# External_Power_Amplifier.net
KiCad netlist of a schematic drawn in Altium Designer
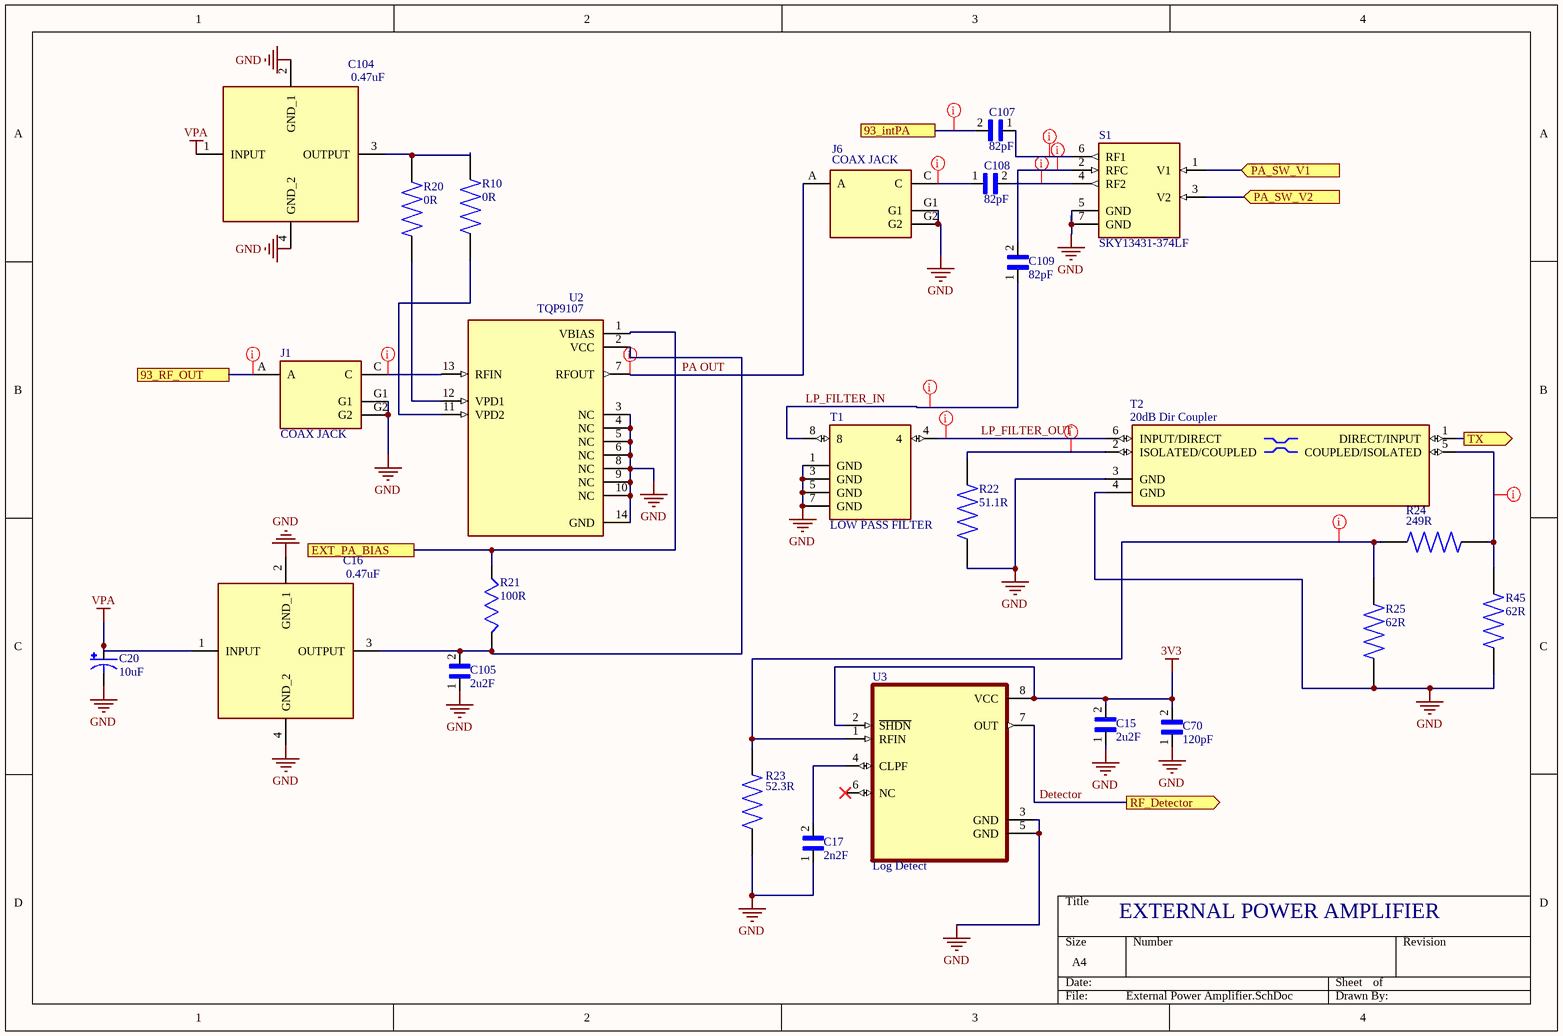
[diagram p0: External Power Amplifier.SchDoc]

(export (version "E")
  (design (tool "Eeschema 10.0.6"))
  (components
    (comp (ref "C15")
      (value "2u2F")
      (footprint "CAPC0603X35N")
      (description "SMD Capacitor X5R(EIA) with Capacitance: 2.2uF Tol. 20%. Rated Voltage: 6.3Vdc")
      (fields (field (name "MP") "GRM033R60J225ME15D"))
      (libsource (lib "GRM033R60J225ME15D") (part "GRM033R60J225ME15D"))
    )
    (comp (ref "C16")
      (value "0.47uF")
      (footprint "SamacSys:NFM18CC101R1C3D")
      (description "Capacitor")
      (fields
        (field (name "MANUFACTURER_PART_NUMBER") "NFM18PS474R0J3D")
        (field (name "MOUSER PART NUMBER") "81-NFM18PS474R0J3D")
      )
      (libsource (lib "*") (part "NFM18PS474R0J3D"))
    )
    (comp (ref "C17")
      (value "2n2F")
      (footprint "CAPC1005X55N")
      (description "SMD capacitor X7R(EIA) with capacitance 2200pF Tol.10%. Rated voltage 50Vdc 125C")
      (fields (field (name "MP") "GRM155R71H222KA01D") (field (name "MF") "Murata"))
      (libsource (lib "GRM155R71H222KA01D") (part "GRM155R71H222KA01D"))
    )
    (comp (ref "C20")
      (value "10uF")
      (footprint "2917(POL)")
      (description "10 ÂµF 16 V Aluminum - Polymer Capacitors 2917 (7343 Metric) 60mOhm 1000 Hrs @ 105Â°C")
      (fields (field (name "MF") "Murata Electronics") (field (name "MP") "ECASD41C106M060K00"))
      (libsource (lib "ECASD41C106M060K00") (part "ECASD41C106M060K00"))
    )
    (comp (ref "C70")
      (value "120pF")
      (footprint "CAPC0603X33N")
      (description "0201 120 pF 50 V Â±5% Tolerance C0G SMT Multilayer Ceramic Capacitor")
      (fields (field (name "MF") "Murata Electronics") (field (name "MP") "GRM0335C1H121JA01D"))
      (libsource (lib "GRM0335C1H121JA01D") (part "GRM0335C1H121JA01D"))
    )
    (comp (ref "C104")
      (value "0.47uF")
      (footprint "SamacSys:NFM18CC101R1C3D")
      (description "Capacitor")
      (fields
        (field (name "MANUFACTURER_PART_NUMBER") "NFM18PS474R0J3D")
        (field (name "MOUSER PART NUMBER") "81-NFM18PS474R0J3D")
      )
      (libsource (lib "*") (part "NFM18PS474R0J3D"))
    )
    (comp (ref "C105")
      (value "2u2F")
      (footprint "CAPC0603X35N")
      (description "SMD Capacitor X5R(EIA) with Capacitance: 2.2uF Tol. 20%. Rated Voltage: 6.3Vdc")
      (fields (field (name "MP") "GRM033R60J225ME15D"))
      (libsource (lib "") (part "GRM033R60J225ME15D_1"))
    )
    (comp (ref "C107")
      (value "82pF")
      (footprint "CAPC1005X55N")
      (description "CAP CER 82PF 50V C0G/NP0 0402")
      (fields (field (name "MP") "GRM1555C1H820GA01J"))
      (libsource (lib "") (part "GRM1555C1H820GA01J_1"))
    )
    (comp (ref "C108")
      (value "82pF")
      (footprint "CAPC1005X55N")
      (description "CAP CER 82PF 50V C0G/NP0 0402")
      (fields (field (name "MP") "GRM1555C1H820GA01J"))
      (libsource (lib "") (part "GRM1555C1H820GA01J_2"))
    )
    (comp (ref "C109")
      (value "82pF")
      (footprint "CAPC1005X55N")
      (description "CAP CER 82PF 50V C0G/NP0 0402")
      (fields (field (name "MP") "GRM1555C1H820GA01J"))
      (libsource (lib "GRM1555C1H820GA01J") (part "GRM1555C1H820GA01J"))
    )
    (comp (ref "J1")
      (value "COAX JACK")
      (footprint "SW_MS-156HF(01)")
      (description "Coaxial Switch - 4mm Plug Dia Connector Receptacle, Female Socket 50Ohm Surface Mount Solder")
      (fields (field (name "MP") "MS-156HF(01)") (field (name "MF") "Hirose Electric"))
      (libsource (lib "MS-156HF_01_") (part "MS-156HF(01)"))
    )
    (comp (ref "J6")
      (value "COAX JACK")
      (footprint "SW_MS-156HF(01)")
      (description "Coaxial Switch - 4mm Plug Dia Connector Receptacle, Female Socket 50Ohm Surface Mount Solder")
      (fields (field (name "MP") "MS-156HF(01)") (field (name "MF") "Hirose Electric"))
      (libsource (lib "MS-156HF_01_") (part "MS-156HF(01)"))
    )
    (comp (ref "R10")
      (value "0R")
      (footprint "RESC1005X37N")
      (fields (field (name "MF") "{'manufacturer': u'YAGEO'}") (field (name "MP") "RC0402JR-070RL"))
      (libsource (lib "RC0402JR-070RL") (part "RC0402JR-070RL"))
    )
    (comp (ref "R20")
      (value "0R")
      (footprint "RESC1005X37N")
      (fields (field (name "MF") "{'manufacturer': u'YAGEO'}") (field (name "MP") "RC0402JR-070RL"))
      (libsource (lib "RC0402JR-070RL") (part "RC0402JR-070RL"))
    )
    (comp (ref "R21")
      (value "100R")
      (footprint "RESC1005X40")
      (description "100 Ohms Â±1% 0.063W, 1/16W Chip Resistor 0402 (1005 Metric) Moisture Resistant Thick Film")
      (fields (field (name "MP") "RC0402FR-07100RL") (field (name "MF") "Yageo"))
      (libsource (lib "RC0402FR-07100RL") (part "RC0402FR-07100RL"))
    )
    (comp (ref "R22")
      (value "51.1R")
      (footprint "RESC1005X40N")
      (description "Res Thick Film 0402 51.1 Ohm 1% 1/16W ?100ppm/C Molded SMD SMD Paper T/R")
      (fields (field (name "MF") "{'manufacturer': u'YAGEO'}") (field (name "MP") "RC0402FR-0751R1L"))
      (libsource (lib "RC0402FR-0751R1L") (part "RC0402FR-0751R1L"))
    )
    (comp (ref "R23")
      (value "52.3R")
      (footprint "RES_ERJ2RKF52R3X")
      (fields (field (name "MP") "ERJ2RKF52R3X"))
      (libsource (lib "ERJ2RKF52R3X") (part "ERJ2RKF52R3X"))
    )
    (comp (ref "R24")
      (value "249R")
      (footprint "RESC1005X40N")
      (description "Res Thick Film 0402 249 Ohm 1% 1/16W ?100ppm/C Molded SMD SMD Paper T/R")
      (fields (field (name "MP") "RC0402FR-07249RL"))
      (libsource (lib "RC0402FR-07249RL") (part "RC0402FR-07249RL"))
    )
    (comp (ref "R25")
      (value "62R")
      (footprint "RESC1005X40N")
      (fields (field (name "MP") "RC0402FR-0762RL"))
      (libsource (lib "RC0402FR-0762RL") (part "RC0402FR-0762RL"))
    )
    (comp (ref "R45")
      (value "62R")
      (footprint "RESC1005X40N")
      (fields (field (name "MP") "RC0402FR-0762RL"))
      (libsource (lib "RC0402FR-0762RL") (part "RC0402FR-0762RL"))
    )
    (comp (ref "S1")
      (value "SKY13431-374LF")
      (footprint "SW_SKY13431-374LF")
      (description "RF Switch IC WiMax, WLAN SPDT 6GHz 50Ohm 6-DFN (1.5x1.5)")
      (fields (field (name "MF") "Skyworks Solutions"))
      (libsource (lib "SKY13431-374LF") (part "SKY13431-374LF"))
    )
    (comp (ref "T1")
      (value "LOW PASS FILTER")
      (footprint "FIL_0900LP15B0063E")
      (fields (field (name "MP") "0900LP15B0063E") (field (name "MF") "Johanson Technology"))
      (libsource (lib "0900LP15B0063E") (part "0900LP15B0063E"))
    )
    (comp (ref "T2")
      (value "20dB Dir Coupler")
      (footprint "COUPLER_DC1722J5020AHF")
      (description "RF Directional Coupler General Purpose 1.7GHz ~ 2.2GHz 19.9dB 2W 0805 (2012 Metric)")
      (fields (field (name "MP") "DC1722J5020AHF") (field (name "MF") "Anaren"))
      (libsource (lib "DC1722J5020AHF") (part "DC1722J5020AHF"))
    )
    (comp (ref "U2")
      (value "TQP9107")
      (footprint "IC_TQP9107")
      (description "RF Amplifier 699-960MHz PAE 31% Gain 35.5dB")
      (fields (field (name "MF") "Qorvo"))
      (libsource (lib "TQP9107") (part "TQP9107"))
    )
    (comp (ref "U3")
      (value "Log Detect")
      (footprint "SOP65P490X110-8N")
      (description "100MHz to 2500MHz, 45dB RF Detector in a UCSP")
      (fields (field (name "MF") "Analog Devices") (field (name "MP") "MAX4003EUA+T"))
      (libsource (lib "MAX4003EUA_T") (part "MAX4003EUA+T"))
    )
  )
  (nets
    (net (code "1") (name "/93_RF_OUT") (class "Default")
      (node (ref "J1") (pin "A") (pinfunction "A_A") (pintype "passive"))
    )
    (net (code "2") (name "/93_intPA") (class "Default")
      (node (ref "C107") (pin "2") (pinfunction "2_2") (pintype "passive"))
    )
    (net (code "3") (name "/Detector") (class "Default")
      (node (ref "U3") (pin "7") (pinfunction "OUT_7") (pintype "output"))
    )
    (net (code "4") (name "/EXT_PA_BIAS") (class "Default")
      (node (ref "R21") (pin "2") (pinfunction "2_2") (pintype "passive"))
      (node (ref "U2") (pin "1") (pinfunction "VBIAS_1") (pintype "power_in"))
    )
    (net (code "5") (name "/LP_FILTER_IN") (class "Default")
      (node (ref "C109") (pin "1") (pinfunction "1_1") (pintype "passive"))
      (node (ref "T1") (pin "8") (pinfunction "8_8") (pintype "bidirectional"))
    )
    (net (code "6") (name "/LP_FILTER_OUT") (class "Default")
      (node (ref "T1") (pin "4") (pinfunction "4_4") (pintype "bidirectional"))
      (node (ref "T2") (pin "6") (pinfunction "INPUT/DIRECT_6") (pintype "bidirectional"))
    )
    (net (code "7") (name "/PA OUT") (class "Default")
      (node (ref "J6") (pin "A") (pinfunction "A_A") (pintype "passive"))
      (node (ref "U2") (pin "7") (pinfunction "RFOUT_7") (pintype "output"))
    )
    (net (code "8") (name "/PA_SW_V1") (class "Default")
      (node (ref "S1") (pin "1") (pinfunction "V1_1") (pintype "input"))
    )
    (net (code "9") (name "/PA_SW_V2") (class "Default")
      (node (ref "S1") (pin "3") (pinfunction "V2_3") (pintype "input"))
    )
    (net (code "10") (name "/TX") (class "Default")
      (node (ref "T2") (pin "1") (pinfunction "DIRECT/INPUT_1") (pintype "bidirectional"))
    )
    (net (code "11") (name "3V3") (class "Default")
      (node (ref "C15") (pin "2") (pinfunction "2_2") (pintype "passive"))
      (node (ref "C70") (pin "2") (pinfunction "2_2") (pintype "passive"))
      (node (ref "U3") (pin "2") (pinfunction "~{SHDN}_2") (pintype "input"))
      (node (ref "U3") (pin "8") (pinfunction "VCC_8") (pintype "power_in"))
    )
    (net (code "12") (name "GND") (class "Default")
      (node (ref "C104") (pin "2") (pinfunction "GND_1_2") (pintype "passive"))
      (node (ref "C104") (pin "4") (pinfunction "GND_2_4") (pintype "passive"))
      (node (ref "C105") (pin "1") (pinfunction "1_1") (pintype "passive"))
      (node (ref "C15") (pin "1") (pinfunction "1_1") (pintype "passive"))
      (node (ref "C16") (pin "2") (pinfunction "GND_1_2") (pintype "passive"))
      (node (ref "C16") (pin "4") (pinfunction "GND_2_4") (pintype "passive"))
      (node (ref "C17") (pin "1") (pinfunction "1_1") (pintype "passive"))
      (node (ref "C20") (pin "2") (pinfunction "NEG_2") (pintype "passive"))
      (node (ref "C70") (pin "1") (pinfunction "1_1") (pintype "passive"))
      (node (ref "J1") (pin "G1") (pinfunction "G1_G1") (pintype "power_in"))
      (node (ref "J1") (pin "G2") (pinfunction "G2_G2") (pintype "power_in"))
      (node (ref "J6") (pin "G1") (pinfunction "G1_G1") (pintype "power_in"))
      (node (ref "J6") (pin "G2") (pinfunction "G2_G2") (pintype "power_in"))
      (node (ref "R22") (pin "1") (pinfunction "1_1") (pintype "passive"))
      (node (ref "R23") (pin "1") (pinfunction "1_1") (pintype "passive"))
      (node (ref "R25") (pin "1") (pinfunction "1_1") (pintype "passive"))
      (node (ref "R45") (pin "1") (pinfunction "1_1") (pintype "passive"))
      (node (ref "S1") (pin "5") (pinfunction "GND_5") (pintype "power_in"))
      (node (ref "S1") (pin "7") (pinfunction "GND_7") (pintype "power_in"))
      (node (ref "T1") (pin "1") (pinfunction "GND_1") (pintype "power_in"))
      (node (ref "T1") (pin "3") (pinfunction "GND_3") (pintype "power_in"))
      (node (ref "T1") (pin "5") (pinfunction "GND_5") (pintype "power_in"))
      (node (ref "T1") (pin "7") (pinfunction "GND_7") (pintype "power_in"))
      (node (ref "T2") (pin "3") (pinfunction "GND_3") (pintype "power_in"))
      (node (ref "T2") (pin "4") (pinfunction "GND_4") (pintype "power_in"))
      (node (ref "U2") (pin "10") (pinfunction "NC_10") (pintype "passive"))
      (node (ref "U2") (pin "14") (pinfunction "GND_14") (pintype "power_in"))
      (node (ref "U2") (pin "3") (pinfunction "NC_3") (pintype "passive"))
      (node (ref "U2") (pin "4") (pinfunction "NC_4") (pintype "passive"))
      (node (ref "U2") (pin "5") (pinfunction "NC_5") (pintype "passive"))
      (node (ref "U2") (pin "6") (pinfunction "NC_6") (pintype "passive"))
      (node (ref "U2") (pin "8") (pinfunction "NC_8") (pintype "passive"))
      (node (ref "U2") (pin "9") (pinfunction "NC_9") (pintype "passive"))
      (node (ref "U3") (pin "3") (pinfunction "GND_3") (pintype "power_in"))
      (node (ref "U3") (pin "5") (pinfunction "GND_5") (pintype "power_in"))
    )
    (net (code "13") (name "Net-(C16-OUTPUT)") (class "Default")
      (node (ref "C105") (pin "2") (pinfunction "2_2") (pintype "passive"))
      (node (ref "C16") (pin "3") (pinfunction "OUTPUT_3") (pintype "passive"))
      (node (ref "R21") (pin "1") (pinfunction "1_1") (pintype "passive"))
      (node (ref "U2") (pin "2") (pinfunction "VCC_2") (pintype "power_in"))
    )
    (net (code "14") (name "Net-(C104-OUTPUT)") (class "Default")
      (node (ref "C104") (pin "3") (pinfunction "OUTPUT_3") (pintype "passive"))
      (node (ref "R10") (pin "2") (pinfunction "2_2") (pintype "passive"))
      (node (ref "R20") (pin "2") (pinfunction "2_2") (pintype "passive"))
    )
    (net (code "15") (name "Net-(C108-Pad1)") (class "Default")
      (node (ref "C108") (pin "1") (pinfunction "1_1") (pintype "passive"))
      (node (ref "J6") (pin "C") (pinfunction "C_C") (pintype "passive"))
    )
    (net (code "16") (name "Net-(S1-RF1)") (class "Default")
      (node (ref "C107") (pin "1") (pinfunction "1_1") (pintype "passive"))
      (node (ref "S1") (pin "6") (pinfunction "RF1_6") (pintype "output"))
    )
    (net (code "17") (name "Net-(S1-RF2)") (class "Default")
      (node (ref "C108") (pin "2") (pinfunction "2_2") (pintype "passive"))
      (node (ref "S1") (pin "4") (pinfunction "RF2_4") (pintype "output"))
    )
    (net (code "18") (name "Net-(S1-RFC)") (class "Default")
      (node (ref "C109") (pin "2") (pinfunction "2_2") (pintype "passive"))
      (node (ref "S1") (pin "2") (pinfunction "RFC_2") (pintype "input"))
    )
    (net (code "19") (name "Net-(T2-COUPLED{slash}ISOLATED)") (class "Default")
      (node (ref "R24") (pin "2") (pinfunction "2_2") (pintype "passive"))
      (node (ref "R45") (pin "2") (pinfunction "2_2") (pintype "passive"))
      (node (ref "T2") (pin "5") (pinfunction "COUPLED/ISOLATED_5") (pintype "bidirectional"))
    )
    (net (code "20") (name "Net-(T2-ISOLATED{slash}COUPLED)") (class "Default")
      (node (ref "R22") (pin "2") (pinfunction "2_2") (pintype "passive"))
      (node (ref "T2") (pin "2") (pinfunction "ISOLATED/COUPLED_2") (pintype "bidirectional"))
    )
    (net (code "21") (name "Net-(U2-RFIN)") (class "Default")
      (node (ref "J1") (pin "C") (pinfunction "C_C") (pintype "passive"))
      (node (ref "U2") (pin "13") (pinfunction "RFIN_13") (pintype "input"))
    )
    (net (code "22") (name "Net-(U2-VPD1)") (class "Default")
      (node (ref "R20") (pin "1") (pinfunction "1_1") (pintype "passive"))
      (node (ref "U2") (pin "12") (pinfunction "VPD1_12") (pintype "input"))
    )
    (net (code "23") (name "Net-(U2-VPD2)") (class "Default")
      (node (ref "R10") (pin "1") (pinfunction "1_1") (pintype "passive"))
      (node (ref "U2") (pin "11") (pinfunction "VPD2_11") (pintype "input"))
    )
    (net (code "24") (name "Net-(U3-CLPF)") (class "Default")
      (node (ref "C17") (pin "2") (pinfunction "2_2") (pintype "passive"))
      (node (ref "U3") (pin "4") (pinfunction "CLPF_4") (pintype "bidirectional"))
    )
    (net (code "25") (name "Net-(U3-RFIN)") (class "Default")
      (node (ref "R23") (pin "2") (pinfunction "2_2") (pintype "passive"))
      (node (ref "R24") (pin "1") (pinfunction "1_1") (pintype "passive"))
      (node (ref "R25") (pin "2") (pinfunction "2_2") (pintype "passive"))
      (node (ref "U3") (pin "1") (pinfunction "RFIN_1") (pintype "input"))
    )
    (net (code "26") (name "VPA") (class "Default")
      (node (ref "C104") (pin "1") (pinfunction "INPUT_1") (pintype "passive"))
      (node (ref "C16") (pin "1") (pinfunction "INPUT_1") (pintype "passive"))
      (node (ref "C20") (pin "1") (pinfunction "POS_1") (pintype "passive"))
    )
    (net (code "27") (name "unconnected-(U3-NC-Pad6)") (class "Default")
      (node (ref "U3") (pin "6") (pinfunction "NC_6") (pintype "bidirectional+no_connect"))
    )
  )
)
